# SolenoidBoard.net
KiCad netlist of a schematic drawn in EAGLE
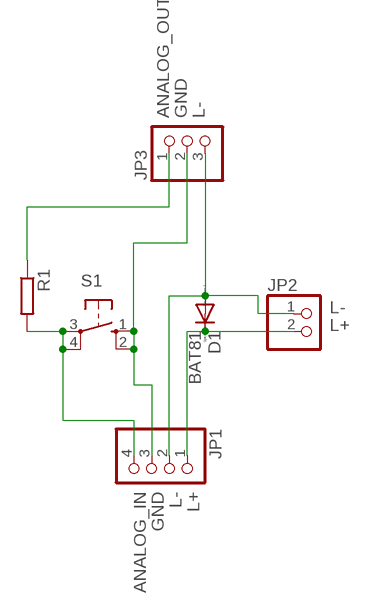
[diagram p0: schematic, sheet 1]

(export (version "E")
  (design (tool "Eeschema 10.0.6"))
  (components
    (comp (ref "D1")
      (value "BAT81")
      (footprint "eagle-import:DO34-7")
      (libsource (lib "eagle-import") (part "BAT81"))
    )
    (comp (ref "JP1")
      (value "PINHD-1X4")
      (footprint "eagle-import:1X04")
      (libsource (lib "eagle-import") (part "PINHD-1X4"))
    )
    (comp (ref "JP2")
      (value "PINHD-1X2")
      (footprint "eagle-import:1X02")
      (libsource (lib "eagle-import") (part "PINHD-1X2"))
    )
    (comp (ref "JP3")
      (value "PINHD-1X3")
      (footprint "eagle-import:1X03")
      (libsource (lib "eagle-import") (part "PINHD-1X3"))
    )
    (comp (ref "R1")
      (value "R-EU_0204/7")
      (footprint "eagle-import:0204_7")
      (libsource (lib "eagle-import") (part "R-EU_0204/7"))
    )
    (comp (ref "S1")
      (value "10-XX")
      (footprint "eagle-import:B3F-10XX")
      (fields (field (name "MPN") "B3F-1000"))
      (libsource (lib "eagle-import") (part "10-XX"))
    )
  )
  (nets
    (net (code "1") (name "/ANALOG_IN") (class "Default")
      (node (ref "JP1") (pin "4") (pinfunction "4_4") (pintype "passive"))
      (node (ref "R1") (pin "2") (pinfunction "2_2") (pintype "passive"))
      (node (ref "S1") (pin "3") (pinfunction "P_3") (pintype "passive"))
      (node (ref "S1") (pin "4") (pinfunction "P1_4") (pintype "passive"))
    )
    (net (code "2") (name "/ANALOG_OUT") (class "Default")
      (node (ref "JP3") (pin "1") (pinfunction "1_1") (pintype "passive"))
      (node (ref "R1") (pin "1") (pinfunction "1_1") (pintype "passive"))
    )
    (net (code "3") (name "/GND") (class "Default")
      (node (ref "JP1") (pin "3") (pinfunction "3_3") (pintype "passive"))
      (node (ref "JP3") (pin "2") (pinfunction "2_2") (pintype "passive"))
      (node (ref "S1") (pin "1") (pinfunction "S_1") (pintype "passive"))
      (node (ref "S1") (pin "2") (pinfunction "S1_2") (pintype "passive"))
    )
    (net (code "4") (name "/L+") (class "Default")
      (node (ref "D1") (pin "C") (pinfunction "C_C") (pintype "passive"))
      (node (ref "JP1") (pin "1") (pinfunction "1_1") (pintype "passive"))
      (node (ref "JP2") (pin "2") (pinfunction "2_2") (pintype "passive"))
    )
    (net (code "5") (name "/L-") (class "Default")
      (node (ref "D1") (pin "A") (pinfunction "A_A") (pintype "passive"))
      (node (ref "JP1") (pin "2") (pinfunction "2_2") (pintype "passive"))
      (node (ref "JP2") (pin "1") (pinfunction "1_1") (pintype "passive"))
      (node (ref "JP3") (pin "3") (pinfunction "3_3") (pintype "passive"))
    )
  )
)
